# untitled.net
KiCad netlist of a schematic drawn in EAGLE
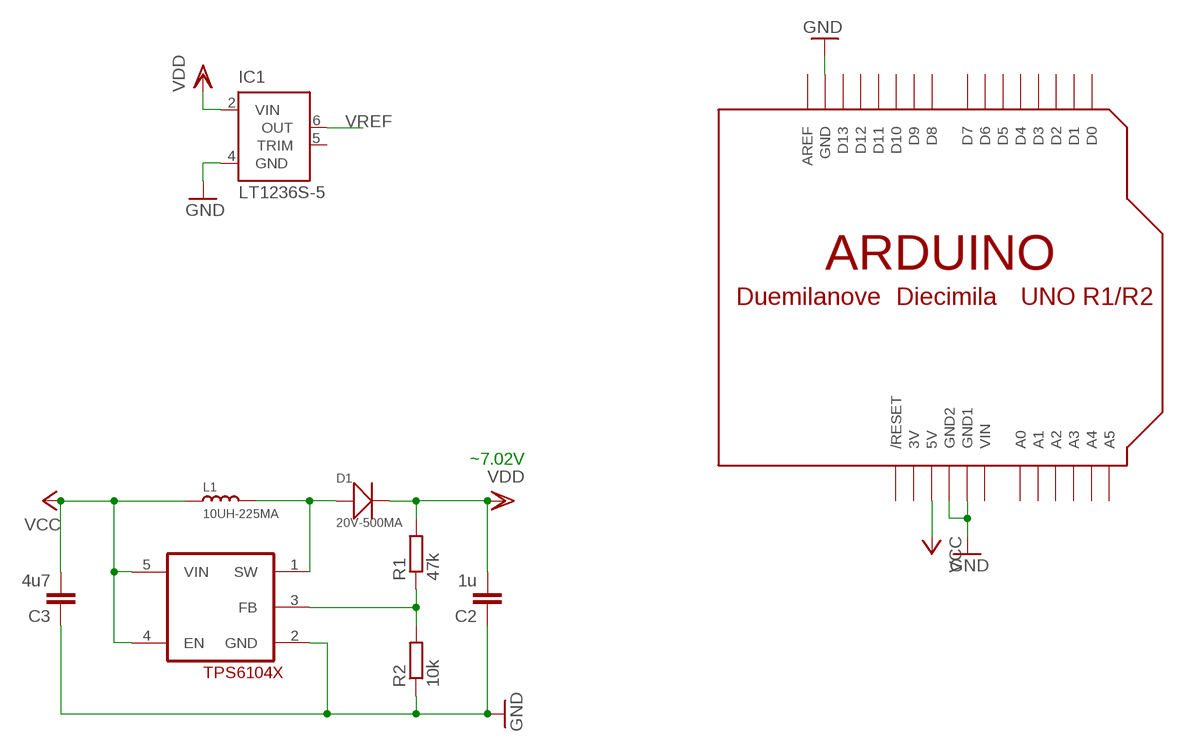
[diagram p0: schematic, sheet 1]

(export (version "E")
  (design (tool "Eeschema 10.0.6"))
  (components
    (comp (ref "C2")
      (value "1u")
      (footprint "eagle-import:C1206")
      (libsource (lib "eagle-import") (part "C-EUC1206"))
    )
    (comp (ref "C3")
      (value "4u7")
      (footprint "eagle-import:C1206")
      (libsource (lib "eagle-import") (part "C-EUC1206"))
    )
    (comp (ref "D1")
      (value "20V-500MA")
      (footprint "eagle-import:SOD-123")
      (fields (field (name "MPN") "MBR0520LT1G"))
      (libsource (lib "eagle-import") (part "SMD-DIODE-SCHOTTKY-20V-500MA(SOD-123)P"))
    )
    (comp (ref "IC1")
      (value "LT1236S-5")
      (footprint "eagle-import:SOIC8")
      (libsource (lib "eagle-import") (part "LT1236?S-5"))
    )
    (comp (ref "L1")
      (value "10UH-225MA")
      (footprint "eagle-import:L0806")
      (fields (field (name "MPN") "LQH2MCN100K02L"))
      (libsource (lib "eagle-import") (part "SMD-INDUCTOR-10UH-225MA-10%(0806)"))
    )
    (comp (ref "R1")
      (value "47k")
      (footprint "eagle-import:R0805")
      (libsource (lib "eagle-import") (part "R-EU_R0805"))
    )
    (comp (ref "R2")
      (value "10k")
      (footprint "eagle-import:R0805")
      (libsource (lib "eagle-import") (part "R-EU_R0805"))
    )
    (comp (ref "U$1")
      (value "ARDUINO-NOHOLE")
      (footprint "eagle-import:ARDUINO-NOHOLE")
      (libsource (lib "eagle-import") (part "ARDUINO-NOHOLE"))
    )
    (comp (ref "U$2")
      (value "TPS6104X")
      (footprint "eagle-import:SOT23-DBV")
      (libsource (lib "eagle-import") (part "TPS6104X"))
    )
  )
  (nets
    (net (code "1") (name "/3V") (class "Default")
      (node (ref "U$1") (pin "3V") (pinfunction "3V_3V") (pintype "power_in"))
    )
    (net (code "2") (name "/VIN") (class "Default")
      (node (ref "U$1") (pin "VIN") (pinfunction "VIN_VIN") (pintype "power_in"))
    )
    (net (code "3") (name "/VREF") (class "Default")
      (node (ref "IC1") (pin "6") (pinfunction "OUT_6") (pintype "input"))
    )
    (net (code "4") (name "GND") (class "Default")
      (node (ref "C2") (pin "1") (pinfunction "1_1") (pintype "passive"))
      (node (ref "C3") (pin "1") (pinfunction "1_1") (pintype "passive"))
      (node (ref "IC1") (pin "4") (pinfunction "GND_4") (pintype "power_in"))
      (node (ref "R2") (pin "1") (pinfunction "1_1") (pintype "passive"))
      (node (ref "U$1") (pin "GND") (pinfunction "GND_GND") (pintype "power_in"))
      (node (ref "U$1") (pin "GND1") (pinfunction "GND1_GND1") (pintype "power_in"))
      (node (ref "U$1") (pin "GND2") (pinfunction "GND2_GND2") (pintype "power_in"))
      (node (ref "U$2") (pin "2") (pinfunction "GND_2") (pintype "bidirectional"))
    )
    (net (code "5") (name "Net-(U$2-FB)") (class "Default")
      (node (ref "R1") (pin "1") (pinfunction "1_1") (pintype "passive"))
      (node (ref "R2") (pin "2") (pinfunction "2_2") (pintype "passive"))
      (node (ref "U$2") (pin "3") (pinfunction "FB_3") (pintype "bidirectional"))
    )
    (net (code "6") (name "Net-(U$2-SW)") (class "Default")
      (node (ref "D1") (pin "+") (pinfunction "+_+") (pintype "passive"))
      (node (ref "L1") (pin "2") (pinfunction "2_2") (pintype "passive"))
      (node (ref "U$2") (pin "1") (pinfunction "SW_1") (pintype "bidirectional"))
    )
    (net (code "7") (name "VCC") (class "Default")
      (node (ref "C3") (pin "2") (pinfunction "2_2") (pintype "passive"))
      (node (ref "L1") (pin "1") (pinfunction "1_1") (pintype "passive"))
      (node (ref "U$1") (pin "5V") (pinfunction "5V_5V") (pintype "power_in"))
      (node (ref "U$2") (pin "4") (pinfunction "EN_4") (pintype "bidirectional"))
      (node (ref "U$2") (pin "5") (pinfunction "VIN_5") (pintype "bidirectional"))
    )
    (net (code "8") (name "VDD") (class "Default")
      (node (ref "C2") (pin "2") (pinfunction "2_2") (pintype "passive"))
      (node (ref "D1") (pin "-") (pinfunction "-_-") (pintype "passive"))
      (node (ref "IC1") (pin "2") (pinfunction "VIN_2") (pintype "input"))
      (node (ref "R1") (pin "2") (pinfunction "2_2") (pintype "passive"))
    )
    (net (code "9") (name "unconnected-(IC1-TRIM-Pad5)") (class "Default")
      (node (ref "IC1") (pin "5") (pinfunction "TRIM_5") (pintype "passive"))
    )
    (net (code "10") (name "unconnected-(U$1-PadA0)") (class "Default")
      (node (ref "U$1") (pin "A0") (pinfunction "A0_A0") (pintype "bidirectional"))
    )
    (net (code "11") (name "unconnected-(U$1-PadA1)") (class "Default")
      (node (ref "U$1") (pin "A1") (pinfunction "A1_A1") (pintype "bidirectional"))
    )
    (net (code "12") (name "unconnected-(U$1-PadA2)") (class "Default")
      (node (ref "U$1") (pin "A2") (pinfunction "A2_A2") (pintype "bidirectional"))
    )
    (net (code "13") (name "unconnected-(U$1-PadA3)") (class "Default")
      (node (ref "U$1") (pin "A3") (pinfunction "A3_A3") (pintype "bidirectional"))
    )
    (net (code "14") (name "unconnected-(U$1-PadA4)") (class "Default")
      (node (ref "U$1") (pin "A4") (pinfunction "A4_A4") (pintype "bidirectional"))
    )
    (net (code "15") (name "unconnected-(U$1-PadA5)") (class "Default")
      (node (ref "U$1") (pin "A5") (pinfunction "A5_A5") (pintype "bidirectional"))
    )
    (net (code "16") (name "unconnected-(U$1-PadAREF)") (class "Default")
      (node (ref "U$1") (pin "AREF") (pinfunction "AREF_AREF") (pintype "bidirectional"))
    )
    (net (code "17") (name "unconnected-(U$1-PadD0)") (class "Default")
      (node (ref "U$1") (pin "D0") (pinfunction "D0_D0") (pintype "bidirectional"))
    )
    (net (code "18") (name "unconnected-(U$1-PadD1)") (class "Default")
      (node (ref "U$1") (pin "D1") (pinfunction "D1_D1") (pintype "bidirectional"))
    )
    (net (code "19") (name "unconnected-(U$1-PadD2)") (class "Default")
      (node (ref "U$1") (pin "D2") (pinfunction "D2_D2") (pintype "bidirectional"))
    )
    (net (code "20") (name "unconnected-(U$1-PadD3)") (class "Default")
      (node (ref "U$1") (pin "D3") (pinfunction "D3_D3") (pintype "bidirectional"))
    )
    (net (code "21") (name "unconnected-(U$1-PadD4)") (class "Default")
      (node (ref "U$1") (pin "D4") (pinfunction "D4_D4") (pintype "bidirectional"))
    )
    (net (code "22") (name "unconnected-(U$1-PadD5)") (class "Default")
      (node (ref "U$1") (pin "D5") (pinfunction "D5_D5") (pintype "bidirectional"))
    )
    (net (code "23") (name "unconnected-(U$1-PadD6)") (class "Default")
      (node (ref "U$1") (pin "D6") (pinfunction "D6_D6") (pintype "bidirectional"))
    )
    (net (code "24") (name "unconnected-(U$1-PadD7)") (class "Default")
      (node (ref "U$1") (pin "D7") (pinfunction "D7_D7") (pintype "bidirectional"))
    )
    (net (code "25") (name "unconnected-(U$1-PadD8)") (class "Default")
      (node (ref "U$1") (pin "D8") (pinfunction "D8_D8") (pintype "bidirectional"))
    )
    (net (code "26") (name "unconnected-(U$1-PadD9)") (class "Default")
      (node (ref "U$1") (pin "D9") (pinfunction "D9_D9") (pintype "bidirectional"))
    )
    (net (code "27") (name "unconnected-(U$1-PadD10)") (class "Default")
      (node (ref "U$1") (pin "D10") (pinfunction "D10_D10") (pintype "bidirectional"))
    )
    (net (code "28") (name "unconnected-(U$1-PadD11)") (class "Default")
      (node (ref "U$1") (pin "D11") (pinfunction "D11_D11") (pintype "bidirectional"))
    )
    (net (code "29") (name "unconnected-(U$1-PadD12)") (class "Default")
      (node (ref "U$1") (pin "D12") (pinfunction "D12_D12") (pintype "bidirectional"))
    )
    (net (code "30") (name "unconnected-(U$1-PadD13)") (class "Default")
      (node (ref "U$1") (pin "D13") (pinfunction "D13_D13") (pintype "bidirectional"))
    )
    (net (code "31") (name "unconnected-(U$1-{slash}RESET-PadRESET)") (class "Default")
      (node (ref "U$1") (pin "RESET") (pinfunction "/RESET_RESET") (pintype "bidirectional"))
    )
  )
)
